# USB_OTG_FS.net
KiCad netlist of a schematic drawn in Altium Designer
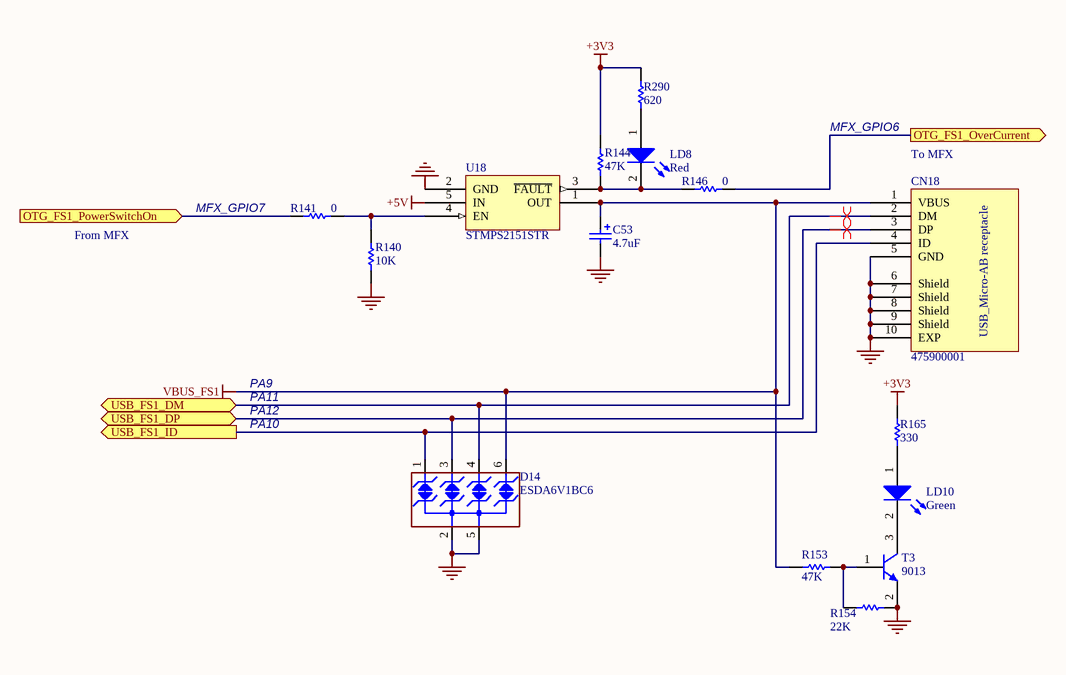
[diagram p0: USB_OTG_FS.SchDoc]

(export (version "E")
  (design (tool "Eeschema 10.0.6"))
  (components
    (comp (ref "C53")
      (value "4.7uF")
      (footprint "TAN-A")
      (description "Polarized Capacitor (Radial)")
      (fields (field (name "PUBLISHER") "Altium Limited"))
      (libsource (lib "Miscellaneous Devices") (part "Cap Pol1"))
    )
    (comp (ref "CN18")
      (value "475900001")
      (footprint "MOLEX_47590001")
      (libsource (lib "mb1045") (part "475900001"))
    )
    (comp (ref "D14")
      (value "ESDA6V1BC6")
      (footprint "STM-SMEE:SOT23-6L")
      (description "Dual Transil array for ESD protection")
      (libsource (lib "MB1137") (part "ESDA6V1BC6"))
    )
    (comp (ref "LD8")
      (value "Red")
      (footprint "0603D")
      (description "Typical RED, GREEN, YELLOW, AMBER GaAs LED")
      (fields (field (name "PUBLISHER") "Altium Limited"))
      (libsource (lib "Miscellaneous Devices") (part "LED2"))
    )
    (comp (ref "LD10")
      (value "Green")
      (footprint "0603D")
      (description "Typical RED, GREEN, YELLOW, AMBER GaAs LED")
      (fields (field (name "PUBLISHER") "Altium Limited"))
      (libsource (lib "Miscellaneous Devices") (part "LED2"))
    )
    (comp (ref "R140")
      (value "10K")
      (footprint "0603R")
      (description "Resistor")
      (fields (field (name "PUBLISHER") "Altium Limited"))
      (libsource (lib "Miscellaneous Devices") (part "Res1"))
    )
    (comp (ref "R141")
      (value "0")
      (footprint "0603R")
      (description "Resistor")
      (fields (field (name "PUBLISHER") "Altium Limited"))
      (libsource (lib "Miscellaneous Devices") (part "Res1"))
    )
    (comp (ref "R144")
      (value "47K")
      (footprint "0603R")
      (description "Resistor")
      (fields (field (name "PUBLISHER") "Altium Limited"))
      (libsource (lib "Miscellaneous Devices") (part "res1"))
    )
    (comp (ref "R146")
      (value "0")
      (footprint "0603R")
      (description "Resistor")
      (fields (field (name "PUBLISHER") "Altium Limited"))
      (libsource (lib "Miscellaneous Devices") (part "Res1"))
    )
    (comp (ref "R153")
      (value "47K")
      (footprint "0603R")
      (description "Resistor")
      (fields (field (name "PUBLISHER") "Altium Limited"))
      (libsource (lib "Miscellaneous Devices") (part "res1"))
    )
    (comp (ref "R154")
      (value "22K")
      (footprint "0603R")
      (description "Resistor")
      (fields (field (name "PUBLISHER") "Altium Limited"))
      (libsource (lib "Miscellaneous Devices") (part "res1"))
    )
    (comp (ref "R165")
      (value "330")
      (footprint "0603R")
      (description "Resistor")
      (fields (field (name "PUBLISHER") "Altium Limited"))
      (libsource (lib "Miscellaneous Devices") (part "res1"))
    )
    (comp (ref "R290")
      (value "620")
      (footprint "0603R")
      (description "Resistor")
      (fields (field (name "PUBLISHER") "Altium Limited"))
      (libsource (lib "Miscellaneous Devices") (part "Res1"))
    )
    (comp (ref "T3")
      (value "9013")
      (footprint "SOT-23")
      (description "NPN Bipolar Transistor")
      (fields (field (name "PUBLISHER") "Altium Limited"))
      (libsource (lib "MB1167") (part "NPN"))
    )
    (comp (ref "U18")
      (value "STMPS2151STR")
      (footprint "SOT23-5")
      (libsource (lib "mb1045") (part "STMPS2141STR"))
    )
  )
  (nets
    (net (code "1") (name "+3V3") (class "Default")
      (node (ref "R144") (pin "1") (pinfunction "1_1") (pintype "passive"))
      (node (ref "R165") (pin "2") (pinfunction "2_2") (pintype "passive"))
      (node (ref "R290") (pin "2") (pinfunction "2_2") (pintype "passive"))
    )
    (net (code "2") (name "+5V") (class "Default")
      (node (ref "U18") (pin "5") (pinfunction "IN_5") (pintype "passive"))
    )
    (net (code "3") (name "/OTG_FS1_OverCurrent") (class "Default")
      (node (ref "R146") (pin "1") (pinfunction "1_1") (pintype "passive"))
    )
    (net (code "4") (name "/OTG_FS1_PowerSwitchOn") (class "Default")
      (node (ref "R141") (pin "2") (pinfunction "2_2") (pintype "passive"))
    )
    (net (code "5") (name "/USB_FS1_DM") (class "Default")
      (node (ref "CN18") (pin "2") (pinfunction "DM_2") (pintype "passive"))
      (node (ref "D14") (pin "4") (pinfunction "IO3_4") (pintype "passive"))
    )
    (net (code "6") (name "/USB_FS1_DP") (class "Default")
      (node (ref "CN18") (pin "3") (pinfunction "DP_3") (pintype "passive"))
      (node (ref "D14") (pin "3") (pinfunction "GND_3") (pintype "passive"))
    )
    (net (code "7") (name "/USB_FS1_ID") (class "Default")
      (node (ref "CN18") (pin "4") (pinfunction "ID_4") (pintype "passive"))
      (node (ref "D14") (pin "1") (pinfunction "IO1_1") (pintype "passive"))
    )
    (net (code "8") (name "GND") (class "Default")
      (node (ref "C53") (pin "2") (pinfunction "2_2") (pintype "passive"))
      (node (ref "CN18") (pin "10") (pinfunction "EXP_10") (pintype "passive"))
      (node (ref "CN18") (pin "5") (pinfunction "GND_5") (pintype "passive"))
      (node (ref "CN18") (pin "6") (pinfunction "Shield_6") (pintype "passive"))
      (node (ref "CN18") (pin "7") (pinfunction "Shield_7") (pintype "passive"))
      (node (ref "CN18") (pin "8") (pinfunction "Shield_8") (pintype "passive"))
      (node (ref "CN18") (pin "9") (pinfunction "Shield_9") (pintype "passive"))
      (node (ref "D14") (pin "2") (pinfunction "IO2_2") (pintype "passive"))
      (node (ref "D14") (pin "5") (pinfunction "IO4_5") (pintype "passive"))
      (node (ref "R140") (pin "1") (pinfunction "1_1") (pintype "passive"))
      (node (ref "R154") (pin "1") (pinfunction "1_1") (pintype "passive"))
      (node (ref "T3") (pin "2") (pinfunction "E_2") (pintype "passive"))
      (node (ref "U18") (pin "2") (pinfunction "GND_2") (pintype "passive"))
    )
    (net (code "9") (name "Net-(LD8-A)") (class "Default")
      (node (ref "LD8") (pin "1") (pinfunction "A_1") (pintype "passive"))
      (node (ref "R290") (pin "1") (pinfunction "1_1") (pintype "passive"))
    )
    (net (code "10") (name "Net-(LD8-K)") (class "Default")
      (node (ref "LD8") (pin "2") (pinfunction "K_2") (pintype "passive"))
      (node (ref "R144") (pin "2") (pinfunction "2_2") (pintype "passive"))
      (node (ref "R146") (pin "2") (pinfunction "2_2") (pintype "passive"))
      (node (ref "U18") (pin "3") (pinfunction "~{FAULT}_3") (pintype "output"))
    )
    (net (code "11") (name "Net-(LD10-A)") (class "Default")
      (node (ref "LD10") (pin "1") (pinfunction "A_1") (pintype "passive"))
      (node (ref "R165") (pin "1") (pinfunction "1_1") (pintype "passive"))
    )
    (net (code "12") (name "Net-(LD10-K)") (class "Default")
      (node (ref "LD10") (pin "2") (pinfunction "K_2") (pintype "passive"))
      (node (ref "T3") (pin "3") (pinfunction "C_3") (pintype "passive"))
    )
    (net (code "13") (name "Net-(T3-B)") (class "Default")
      (node (ref "R153") (pin "2") (pinfunction "2_2") (pintype "passive"))
      (node (ref "R154") (pin "2") (pinfunction "2_2") (pintype "passive"))
      (node (ref "T3") (pin "1") (pinfunction "B_1") (pintype "passive"))
    )
    (net (code "14") (name "Net-(U18-EN)") (class "Default")
      (node (ref "R140") (pin "2") (pinfunction "2_2") (pintype "passive"))
      (node (ref "R141") (pin "1") (pinfunction "1_1") (pintype "passive"))
      (node (ref "U18") (pin "4") (pinfunction "EN_4") (pintype "input"))
    )
    (net (code "15") (name "VBUS_FS1") (class "Default")
      (node (ref "C53") (pin "1") (pinfunction "1_1") (pintype "passive"))
      (node (ref "CN18") (pin "1") (pinfunction "VBUS_1") (pintype "passive"))
      (node (ref "D14") (pin "6") (pinfunction "NC_6") (pintype "passive"))
      (node (ref "R153") (pin "1") (pinfunction "1_1") (pintype "passive"))
      (node (ref "U18") (pin "1") (pinfunction "OUT_1") (pintype "passive"))
    )
  )
)
